# analog_out.net
KiCad netlist of a schematic drawn in EAGLE
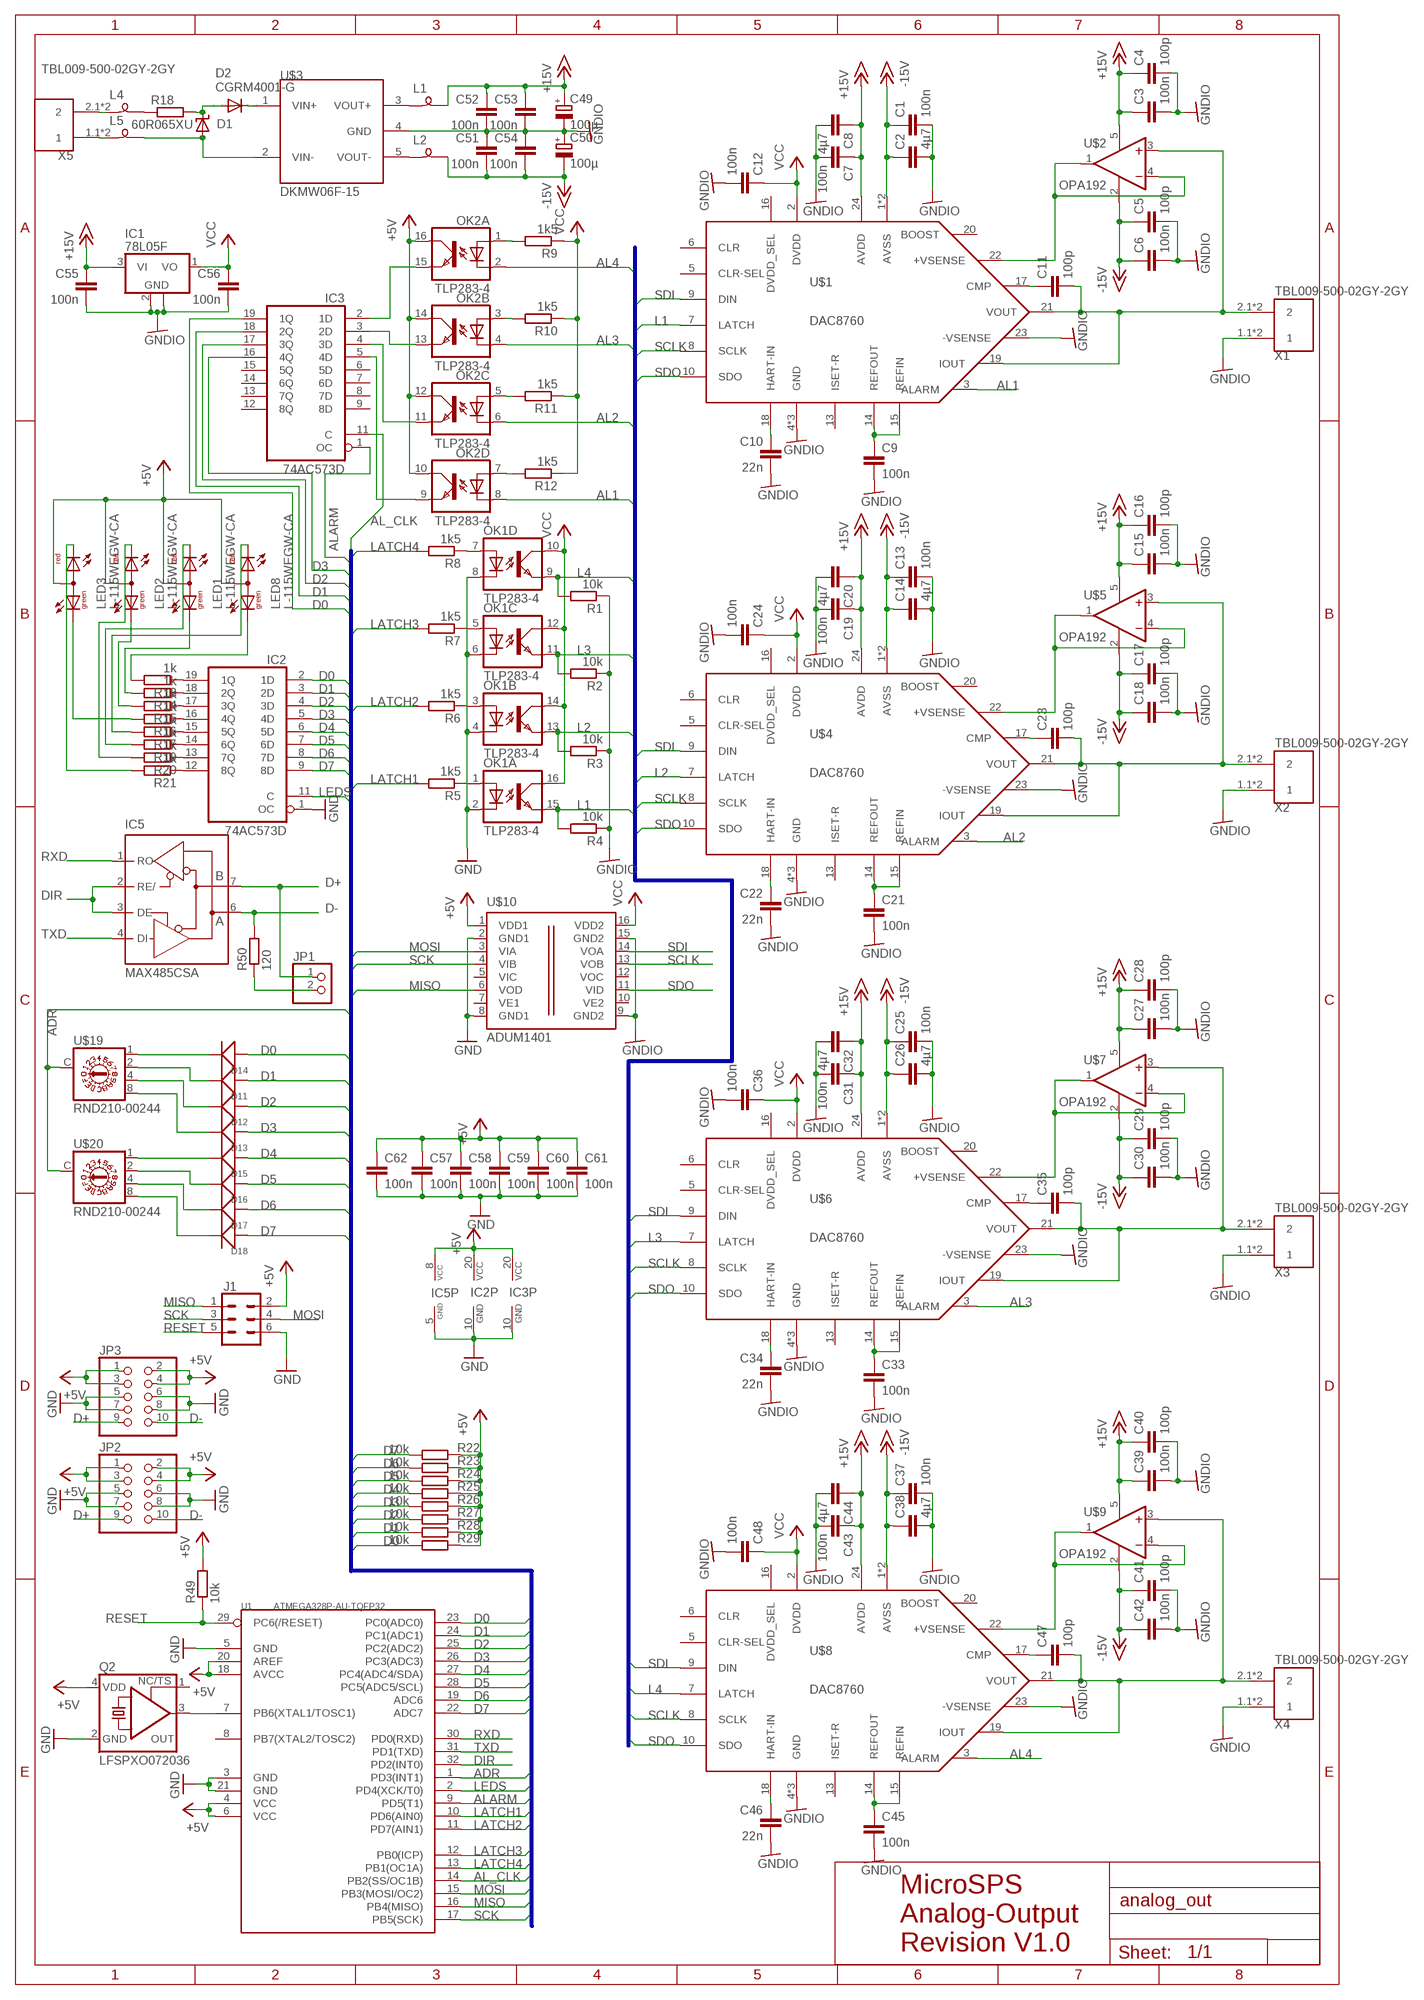
[diagram p0: schematic, sheet 1]

(export (version "E")
  (design (tool "Eeschema 10.0.6"))
  (components
    (comp (ref "C1")
      (value "100n")
      (footprint "eagle-import:C0805")
      (libsource (lib "eagle-import") (part "C-EUC0805"))
    )
    (comp (ref "C2")
      (value "4µ7")
      (footprint "eagle-import:C0805")
      (libsource (lib "eagle-import") (part "C-EUC0805"))
    )
    (comp (ref "C3")
      (value "100n")
      (footprint "eagle-import:C0805")
      (libsource (lib "eagle-import") (part "C-EUC0805"))
    )
    (comp (ref "C4")
      (value "100p")
      (footprint "eagle-import:C0805")
      (libsource (lib "eagle-import") (part "C-EUC0805"))
    )
    (comp (ref "C5")
      (value "100p")
      (footprint "eagle-import:C0805")
      (libsource (lib "eagle-import") (part "C-EUC0805"))
    )
    (comp (ref "C6")
      (value "100n")
      (footprint "eagle-import:C0805")
      (libsource (lib "eagle-import") (part "C-EUC0805"))
    )
    (comp (ref "C7")
      (value "100n")
      (footprint "eagle-import:C0805")
      (libsource (lib "eagle-import") (part "C-EUC0805"))
    )
    (comp (ref "C8")
      (value "4µ7")
      (footprint "eagle-import:C0805")
      (libsource (lib "eagle-import") (part "C-EUC0805"))
    )
    (comp (ref "C9")
      (value "100n")
      (footprint "eagle-import:C0805")
      (libsource (lib "eagle-import") (part "C-EUC0805"))
    )
    (comp (ref "C10")
      (value "22n")
      (footprint "eagle-import:C0805")
      (libsource (lib "eagle-import") (part "C-EUC0805"))
    )
    (comp (ref "C11")
      (value "100p")
      (footprint "eagle-import:C0805")
      (libsource (lib "eagle-import") (part "C-EUC0805"))
    )
    (comp (ref "C12")
      (value "100n")
      (footprint "eagle-import:C0805")
      (libsource (lib "eagle-import") (part "C-EUC0805"))
    )
    (comp (ref "C13")
      (value "100n")
      (footprint "eagle-import:C0805")
      (libsource (lib "eagle-import") (part "C-EUC0805"))
    )
    (comp (ref "C14")
      (value "4µ7")
      (footprint "eagle-import:C0805")
      (libsource (lib "eagle-import") (part "C-EUC0805"))
    )
    (comp (ref "C15")
      (value "100n")
      (footprint "eagle-import:C0805")
      (libsource (lib "eagle-import") (part "C-EUC0805"))
    )
    (comp (ref "C16")
      (value "100p")
      (footprint "eagle-import:C0805")
      (libsource (lib "eagle-import") (part "C-EUC0805"))
    )
    (comp (ref "C17")
      (value "100p")
      (footprint "eagle-import:C0805")
      (libsource (lib "eagle-import") (part "C-EUC0805"))
    )
    (comp (ref "C18")
      (value "100n")
      (footprint "eagle-import:C0805")
      (libsource (lib "eagle-import") (part "C-EUC0805"))
    )
    (comp (ref "C19")
      (value "100n")
      (footprint "eagle-import:C0805")
      (libsource (lib "eagle-import") (part "C-EUC0805"))
    )
    (comp (ref "C20")
      (value "4µ7")
      (footprint "eagle-import:C0805")
      (libsource (lib "eagle-import") (part "C-EUC0805"))
    )
    (comp (ref "C21")
      (value "100n")
      (footprint "eagle-import:C0805")
      (libsource (lib "eagle-import") (part "C-EUC0805"))
    )
    (comp (ref "C22")
      (value "22n")
      (footprint "eagle-import:C0805")
      (libsource (lib "eagle-import") (part "C-EUC0805"))
    )
    (comp (ref "C23")
      (value "100p")
      (footprint "eagle-import:C0805")
      (libsource (lib "eagle-import") (part "C-EUC0805"))
    )
    (comp (ref "C24")
      (value "100n")
      (footprint "eagle-import:C0805")
      (libsource (lib "eagle-import") (part "C-EUC0805"))
    )
    (comp (ref "C25")
      (value "100n")
      (footprint "eagle-import:C0805")
      (libsource (lib "eagle-import") (part "C-EUC0805"))
    )
    (comp (ref "C26")
      (value "4µ7")
      (footprint "eagle-import:C0805")
      (libsource (lib "eagle-import") (part "C-EUC0805"))
    )
    (comp (ref "C27")
      (value "100n")
      (footprint "eagle-import:C0805")
      (libsource (lib "eagle-import") (part "C-EUC0805"))
    )
    (comp (ref "C28")
      (value "100p")
      (footprint "eagle-import:C0805")
      (libsource (lib "eagle-import") (part "C-EUC0805"))
    )
    (comp (ref "C29")
      (value "100p")
      (footprint "eagle-import:C0805")
      (libsource (lib "eagle-import") (part "C-EUC0805"))
    )
    (comp (ref "C30")
      (value "100n")
      (footprint "eagle-import:C0805")
      (libsource (lib "eagle-import") (part "C-EUC0805"))
    )
    (comp (ref "C31")
      (value "100n")
      (footprint "eagle-import:C0805")
      (libsource (lib "eagle-import") (part "C-EUC0805"))
    )
    (comp (ref "C32")
      (value "4µ7")
      (footprint "eagle-import:C0805")
      (libsource (lib "eagle-import") (part "C-EUC0805"))
    )
    (comp (ref "C33")
      (value "100n")
      (footprint "eagle-import:C0805")
      (libsource (lib "eagle-import") (part "C-EUC0805"))
    )
    (comp (ref "C34")
      (value "22n")
      (footprint "eagle-import:C0805")
      (libsource (lib "eagle-import") (part "C-EUC0805"))
    )
    (comp (ref "C35")
      (value "100p")
      (footprint "eagle-import:C0805")
      (libsource (lib "eagle-import") (part "C-EUC0805"))
    )
    (comp (ref "C36")
      (value "100n")
      (footprint "eagle-import:C0805")
      (libsource (lib "eagle-import") (part "C-EUC0805"))
    )
    (comp (ref "C37")
      (value "100n")
      (footprint "eagle-import:C0805")
      (libsource (lib "eagle-import") (part "C-EUC0805"))
    )
    (comp (ref "C38")
      (value "4µ7")
      (footprint "eagle-import:C0805")
      (libsource (lib "eagle-import") (part "C-EUC0805"))
    )
    (comp (ref "C39")
      (value "100n")
      (footprint "eagle-import:C0805")
      (libsource (lib "eagle-import") (part "C-EUC0805"))
    )
    (comp (ref "C40")
      (value "100p")
      (footprint "eagle-import:C0805")
      (libsource (lib "eagle-import") (part "C-EUC0805"))
    )
    (comp (ref "C41")
      (value "100p")
      (footprint "eagle-import:C0805")
      (libsource (lib "eagle-import") (part "C-EUC0805"))
    )
    (comp (ref "C42")
      (value "100n")
      (footprint "eagle-import:C0805")
      (libsource (lib "eagle-import") (part "C-EUC0805"))
    )
    (comp (ref "C43")
      (value "100n")
      (footprint "eagle-import:C0805")
      (libsource (lib "eagle-import") (part "C-EUC0805"))
    )
    (comp (ref "C44")
      (value "4µ7")
      (footprint "eagle-import:C0805")
      (libsource (lib "eagle-import") (part "C-EUC0805"))
    )
    (comp (ref "C45")
      (value "100n")
      (footprint "eagle-import:C0805")
      (libsource (lib "eagle-import") (part "C-EUC0805"))
    )
    (comp (ref "C46")
      (value "22n")
      (footprint "eagle-import:C0805")
      (libsource (lib "eagle-import") (part "C-EUC0805"))
    )
    (comp (ref "C47")
      (value "100p")
      (footprint "eagle-import:C0805")
      (libsource (lib "eagle-import") (part "C-EUC0805"))
    )
    (comp (ref "C48")
      (value "100n")
      (footprint "eagle-import:C0805")
      (libsource (lib "eagle-import") (part "C-EUC0805"))
    )
    (comp (ref "C49")
      (value "100µ")
      (footprint "eagle-import:153CLV-0505")
      (libsource (lib "eagle-import") (part "CPOL-EU153CLV-0505"))
    )
    (comp (ref "C50")
      (value "100µ")
      (footprint "eagle-import:153CLV-0505")
      (libsource (lib "eagle-import") (part "CPOL-EU153CLV-0505"))
    )
    (comp (ref "C51")
      (value "100n")
      (footprint "eagle-import:C0805")
      (libsource (lib "eagle-import") (part "C-EUC0805"))
    )
    (comp (ref "C52")
      (value "100n")
      (footprint "eagle-import:C0805")
      (libsource (lib "eagle-import") (part "C-EUC0805"))
    )
    (comp (ref "C53")
      (value "100n")
      (footprint "eagle-import:C0805")
      (libsource (lib "eagle-import") (part "C-EUC0805"))
    )
    (comp (ref "C54")
      (value "100n")
      (footprint "eagle-import:C0805")
      (libsource (lib "eagle-import") (part "C-EUC0805"))
    )
    (comp (ref "C55")
      (value "100n")
      (footprint "eagle-import:C0805")
      (libsource (lib "eagle-import") (part "C-EUC0805"))
    )
    (comp (ref "C56")
      (value "100n")
      (footprint "eagle-import:C0805")
      (libsource (lib "eagle-import") (part "C-EUC0805"))
    )
    (comp (ref "C57")
      (value "100n")
      (footprint "eagle-import:C0805")
      (libsource (lib "eagle-import") (part "C-EUC0805"))
    )
    (comp (ref "C58")
      (value "100n")
      (footprint "eagle-import:C0805")
      (libsource (lib "eagle-import") (part "C-EUC0805"))
    )
    (comp (ref "C59")
      (value "100n")
      (footprint "eagle-import:C0805")
      (libsource (lib "eagle-import") (part "C-EUC0805"))
    )
    (comp (ref "C60")
      (value "100n")
      (footprint "eagle-import:C0805")
      (libsource (lib "eagle-import") (part "C-EUC0805"))
    )
    (comp (ref "C61")
      (value "100n")
      (footprint "eagle-import:C0805")
      (libsource (lib "eagle-import") (part "C-EUC0805"))
    )
    (comp (ref "C62")
      (value "100n")
      (footprint "eagle-import:C0805")
      (libsource (lib "eagle-import") (part "C-EUC0805"))
    )
    (comp (ref "D1")
      (value "SUPPRESSOR-SMBJ")
      (footprint "eagle-import:SMBJ")
      (libsource (lib "eagle-import") (part "SUPPRESSOR-SMBJ"))
    )
    (comp (ref "D2")
      (value "CGRM4001-G")
      (footprint "eagle-import:SOD-123_MINI-SMA")
      (libsource (lib "eagle-import") (part "CGRM400-G1"))
    )
    (comp (ref "D11")
      (value "DIODE'1N4148-SMD'")
      (footprint "eagle-import:LL-34")
      (libsource (lib "eagle-import") (part "DIODE'1N4148-SMD'"))
    )
    (comp (ref "D12")
      (value "DIODE'1N4148-SMD'")
      (footprint "eagle-import:LL-34")
      (libsource (lib "eagle-import") (part "DIODE'1N4148-SMD'"))
    )
    (comp (ref "D13")
      (value "DIODE'1N4148-SMD'")
      (footprint "eagle-import:LL-34")
      (libsource (lib "eagle-import") (part "DIODE'1N4148-SMD'"))
    )
    (comp (ref "D14")
      (value "DIODE'1N4148-SMD'")
      (footprint "eagle-import:LL-34")
      (libsource (lib "eagle-import") (part "DIODE'1N4148-SMD'"))
    )
    (comp (ref "D15")
      (value "DIODE'1N4148-SMD'")
      (footprint "eagle-import:LL-34")
      (libsource (lib "eagle-import") (part "DIODE'1N4148-SMD'"))
    )
    (comp (ref "D16")
      (value "DIODE'1N4148-SMD'")
      (footprint "eagle-import:LL-34")
      (libsource (lib "eagle-import") (part "DIODE'1N4148-SMD'"))
    )
    (comp (ref "D17")
      (value "DIODE'1N4148-SMD'")
      (footprint "eagle-import:LL-34")
      (libsource (lib "eagle-import") (part "DIODE'1N4148-SMD'"))
    )
    (comp (ref "D18")
      (value "DIODE'1N4148-SMD'")
      (footprint "eagle-import:LL-34")
      (libsource (lib "eagle-import") (part "DIODE'1N4148-SMD'"))
    )
    (comp (ref "IC1")
      (value "78L05F")
      (footprint "eagle-import:SOT89")
      (libsource (lib "eagle-import") (part "78LF05"))
    )
    (comp (ref "IC2")
      (value "74AC573D")
      (footprint "eagle-import:SO20W")
      (libsource (lib "eagle-import") (part "74573DAC"))
    )
    (comp (ref "IC3")
      (value "74AC573D")
      (footprint "eagle-import:SO20W")
      (libsource (lib "eagle-import") (part "74573DAC"))
    )
    (comp (ref "IC5")
      (value "MAX485CSA")
      (footprint "eagle-import:SO08")
      (fields (field (name "MF") "MAXIM") (field (name "MPN") "MAX481CSA"))
      (libsource (lib "eagle-import") (part "MAX481CSA"))
    )
    (comp (ref "J1")
      (value "CONN_03X2FEMALE_SMD")
      (footprint "eagle-import:2X3_SMD")
      (libsource (lib "eagle-import") (part "CONN_03X2FEMALE_SMD"))
    )
    (comp (ref "JP1")
      (value "PINHD-1X2")
      (footprint "eagle-import:1X02")
      (libsource (lib "eagle-import") (part "PINHD-1X2"))
    )
    (comp (ref "JP2")
      (value "PINHD-2X5/90")
      (footprint "eagle-import:2X05_90")
      (libsource (lib "eagle-import") (part "PINHD-2X5/90"))
    )
    (comp (ref "JP3")
      (value "PINHD-2X5/90")
      (footprint "eagle-import:2X05_90")
      (libsource (lib "eagle-import") (part "PINHD-2X5/90"))
    )
    (comp (ref "L1")
      (value "SM-B5")
      (footprint "eagle-import:SM-B5")
      (libsource (lib "eagle-import") (part "SM-B5"))
    )
    (comp (ref "L2")
      (value "SM-B5")
      (footprint "eagle-import:SM-B5")
      (libsource (lib "eagle-import") (part "SM-B5"))
    )
    (comp (ref "L4")
      (value "SM-B5")
      (footprint "eagle-import:SM-B5")
      (libsource (lib "eagle-import") (part "SM-B5"))
    )
    (comp (ref "L5")
      (value "SM-B5")
      (footprint "eagle-import:SM-B5")
      (libsource (lib "eagle-import") (part "SM-B5"))
    )
    (comp (ref "LED1")
      (value "L-115WEGW-CA")
      (footprint "eagle-import:DUOLED-A-3MM")
      (libsource (lib "eagle-import") (part "L-115WEGW-CA"))
    )
    (comp (ref "LED2")
      (value "L-115WEGW-CA")
      (footprint "eagle-import:DUOLED-A-3MM")
      (libsource (lib "eagle-import") (part "L-115WEGW-CA"))
    )
    (comp (ref "LED3")
      (value "L-115WEGW-CA")
      (footprint "eagle-import:DUOLED-A-3MM")
      (libsource (lib "eagle-import") (part "L-115WEGW-CA"))
    )
    (comp (ref "LED8")
      (value "L-115WEGW-CA")
      (footprint "eagle-import:DUOLED-A-3MM")
      (libsource (lib "eagle-import") (part "L-115WEGW-CA"))
    )
    (comp (ref "OK1")
      (value "TLP283-4")
      (footprint "eagle-import:MINI-FLAT-16")
      (libsource (lib "eagle-import") (part "TLP283-4"))
    )
    (comp (ref "OK2")
      (value "TLP283-4")
      (footprint "eagle-import:MINI-FLAT-16")
      (libsource (lib "eagle-import") (part "TLP283-4"))
    )
    (comp (ref "Q2")
      (value "LFSPXO072036")
      (footprint "eagle-import:5.0X3.2_KXO-56")
      (libsource (lib "eagle-import") (part "KXO-PXO/XO-56-56"))
    )
    (comp (ref "R1")
      (value "10k")
      (footprint "eagle-import:R0805")
      (libsource (lib "eagle-import") (part "R-EU_R0805"))
    )
    (comp (ref "R2")
      (value "10k")
      (footprint "eagle-import:R0805")
      (libsource (lib "eagle-import") (part "R-EU_R0805"))
    )
    (comp (ref "R3")
      (value "10k")
      (footprint "eagle-import:R0805")
      (libsource (lib "eagle-import") (part "R-EU_R0805"))
    )
    (comp (ref "R4")
      (value "10k")
      (footprint "eagle-import:R0805")
      (libsource (lib "eagle-import") (part "R-EU_R0805"))
    )
    (comp (ref "R5")
      (value "1k5")
      (footprint "eagle-import:R0805")
      (libsource (lib "eagle-import") (part "R-EU_R0805"))
    )
    (comp (ref "R6")
      (value "1k5")
      (footprint "eagle-import:R0805")
      (libsource (lib "eagle-import") (part "R-EU_R0805"))
    )
    (comp (ref "R7")
      (value "1k5")
      (footprint "eagle-import:R0805")
      (libsource (lib "eagle-import") (part "R-EU_R0805"))
    )
    (comp (ref "R8")
      (value "1k5")
      (footprint "eagle-import:R0805")
      (libsource (lib "eagle-import") (part "R-EU_R0805"))
    )
    (comp (ref "R9")
      (value "1k5")
      (footprint "eagle-import:R0805")
      (libsource (lib "eagle-import") (part "R-EU_R0805"))
    )
    (comp (ref "R10")
      (value "1k5")
      (footprint "eagle-import:R0805")
      (libsource (lib "eagle-import") (part "R-EU_R0805"))
    )
    (comp (ref "R11")
      (value "1k5")
      (footprint "eagle-import:R0805")
      (libsource (lib "eagle-import") (part "R-EU_R0805"))
    )
    (comp (ref "R12")
      (value "1k5")
      (footprint "eagle-import:R0805")
      (libsource (lib "eagle-import") (part "R-EU_R0805"))
    )
    (comp (ref "R13")
      (value "1k")
      (footprint "eagle-import:R0805")
      (libsource (lib "eagle-import") (part "R-EU_R0805"))
    )
    (comp (ref "R14")
      (value "1k")
      (footprint "eagle-import:R0805")
      (libsource (lib "eagle-import") (part "R-EU_R0805"))
    )
    (comp (ref "R15")
      (value "1k")
      (footprint "eagle-import:R0805")
      (libsource (lib "eagle-import") (part "R-EU_R0805"))
    )
    (comp (ref "R16")
      (value "1k")
      (footprint "eagle-import:R0805")
      (libsource (lib "eagle-import") (part "R-EU_R0805"))
    )
    (comp (ref "R17")
      (value "1k")
      (footprint "eagle-import:R0805")
      (libsource (lib "eagle-import") (part "R-EU_R0805"))
    )
    (comp (ref "R18")
      (value "60R065XU")
      (footprint "eagle-import:0204_5")
      (libsource (lib "eagle-import") (part "R-EU_0204/5"))
    )
    (comp (ref "R19")
      (value "1k")
      (footprint "eagle-import:R0805")
      (libsource (lib "eagle-import") (part "R-EU_R0805"))
    )
    (comp (ref "R20")
      (value "1k")
      (footprint "eagle-import:R0805")
      (libsource (lib "eagle-import") (part "R-EU_R0805"))
    )
    (comp (ref "R21")
      (value "1k")
      (footprint "eagle-import:R0805")
      (libsource (lib "eagle-import") (part "R-EU_R0805"))
    )
    (comp (ref "R22")
      (value "10k")
      (footprint "eagle-import:R0805")
      (libsource (lib "eagle-import") (part "R-EU_R0805"))
    )
    (comp (ref "R23")
      (value "10k")
      (footprint "eagle-import:R0805")
      (libsource (lib "eagle-import") (part "R-EU_R0805"))
    )
    (comp (ref "R24")
      (value "10k")
      (footprint "eagle-import:R0805")
      (libsource (lib "eagle-import") (part "R-EU_R0805"))
    )
    (comp (ref "R25")
      (value "10k")
      (footprint "eagle-import:R0805")
      (libsource (lib "eagle-import") (part "R-EU_R0805"))
    )
    (comp (ref "R26")
      (value "10k")
      (footprint "eagle-import:R0805")
      (libsource (lib "eagle-import") (part "R-EU_R0805"))
    )
    (comp (ref "R27")
      (value "10k")
      (footprint "eagle-import:R0805")
      (libsource (lib "eagle-import") (part "R-EU_R0805"))
    )
    (comp (ref "R28")
      (value "10k")
      (footprint "eagle-import:R0805")
      (libsource (lib "eagle-import") (part "R-EU_R0805"))
    )
    (comp (ref "R29")
      (value "10k")
      (footprint "eagle-import:R0805")
      (libsource (lib "eagle-import") (part "R-EU_R0805"))
    )
    (comp (ref "R49")
      (value "10k")
      (footprint "eagle-import:R0805")
      (libsource (lib "eagle-import") (part "R-EU_R0805"))
    )
    (comp (ref "R50")
      (value "120")
      (footprint "eagle-import:R0805")
      (libsource (lib "eagle-import") (part "R-EU_R0805"))
    )
    (comp (ref "U$1")
      (value "DAC8760")
      (footprint "eagle-import:HTSSOP24PWP")
      (libsource (lib "eagle-import") (part "DAC8760"))
    )
    (comp (ref "U$2")
      (value "OPA192")
      (footprint "eagle-import:SOT23-DBV")
      (libsource (lib "eagle-import") (part "OPA192"))
    )
    (comp (ref "U$3")
      (value "DKMW06F-15")
      (footprint "eagle-import:DKWM06")
      (libsource (lib "eagle-import") (part "DKMW06F-15"))
    )
    (comp (ref "U$4")
      (value "DAC8760")
      (footprint "eagle-import:HTSSOP24PWP")
      (libsource (lib "eagle-import") (part "DAC8760"))
    )
    (comp (ref "U$5")
      (value "OPA192")
      (footprint "eagle-import:SOT23-DBV")
      (libsource (lib "eagle-import") (part "OPA192"))
    )
    (comp (ref "U$6")
      (value "DAC8760")
      (footprint "eagle-import:HTSSOP24PWP")
      (libsource (lib "eagle-import") (part "DAC8760"))
    )
    (comp (ref "U$7")
      (value "OPA192")
      (footprint "eagle-import:SOT23-DBV")
      (libsource (lib "eagle-import") (part "OPA192"))
    )
    (comp (ref "U$8")
      (value "DAC8760")
      (footprint "eagle-import:HTSSOP24PWP")
      (libsource (lib "eagle-import") (part "DAC8760"))
    )
    (comp (ref "U$9")
      (value "OPA192")
      (footprint "eagle-import:SOT23-DBV")
      (libsource (lib "eagle-import") (part "OPA192"))
    )
    (comp (ref "U$10")
      (value "ADUM1401")
      (footprint "eagle-import:SO-16W")
      (libsource (lib "eagle-import") (part "ADUM1401"))
    )
    (comp (ref "U$19")
      (value "RND210-00244")
      (footprint "eagle-import:RND210-00244")
      (libsource (lib "eagle-import") (part "RND210-00244"))
    )
    (comp (ref "U$20")
      (value "RND210-00244")
      (footprint "eagle-import:RND210-00244")
      (libsource (lib "eagle-import") (part "RND210-00244"))
    )
    (comp (ref "U1")
      (value "ATMEGA328P-AU-TQFP32")
      (footprint "eagle-import:TQFP32-0.8-7X7MM")
      (fields (field (name "MPN") "ATMEGA328P-AU"))
      (libsource (lib "eagle-import") (part "MCU-ATMEGA328P-AU(TQFP32)"))
    )
    (comp (ref "X1")
      (value "TBL009-500-02GY-2GY")
      (footprint "eagle-import:TBL009-500-02GY-2GY")
      (libsource (lib "eagle-import") (part "TBL009-500-02GY-2GY"))
    )
    (comp (ref "X2")
      (value "TBL009-500-02GY-2GY")
      (footprint "eagle-import:TBL009-500-02GY-2GY")
      (libsource (lib "eagle-import") (part "TBL009-500-02GY-2GY"))
    )
    (comp (ref "X3")
      (value "TBL009-500-02GY-2GY")
      (footprint "eagle-import:TBL009-500-02GY-2GY")
      (libsource (lib "eagle-import") (part "TBL009-500-02GY-2GY"))
    )
    (comp (ref "X4")
      (value "TBL009-500-02GY-2GY")
      (footprint "eagle-import:TBL009-500-02GY-2GY")
      (libsource (lib "eagle-import") (part "TBL009-500-02GY-2GY"))
    )
    (comp (ref "X5")
      (value "TBL009-500-02GY-2GY")
      (footprint "eagle-import:TBL009-500-02GY-2GY")
      (libsource (lib "eagle-import") (part "TBL009-500-02GY-2GY"))
    )
  )
  (nets
    (net (code "1") (name "+5V") (class "Default")
      (node (ref "C57") (pin "1") (pinfunction "1_1") (pintype "passive"))
      (node (ref "C58") (pin "1") (pinfunction "1_1") (pintype "passive"))
      (node (ref "C59") (pin "1") (pinfunction "1_1") (pintype "passive"))
      (node (ref "C60") (pin "1") (pinfunction "1_1") (pintype "passive"))
      (node (ref "C61") (pin "1") (pinfunction "1_1") (pintype "passive"))
      (node (ref "C62") (pin "1") (pinfunction "1_1") (pintype "passive"))
      (node (ref "IC2") (pin "20") (pinfunction "VCC_20") (pintype "power_in"))
      (node (ref "IC3") (pin "20") (pinfunction "VCC_20") (pintype "power_in"))
      (node (ref "IC5") (pin "8") (pinfunction "VCC_8") (pintype "power_in"))
      (node (ref "J1") (pin "2") (pinfunction "2_2") (pintype "bidirectional"))
      (node (ref "JP2") (pin "1") (pinfunction "1_1") (pintype "passive"))
      (node (ref "JP2") (pin "2") (pinfunction "2_2") (pintype "passive"))
      (node (ref "JP2") (pin "3") (pinfunction "3_3") (pintype "passive"))
      (node (ref "JP2") (pin "4") (pinfunction "4_4") (pintype "passive"))
      (node (ref "JP3") (pin "1") (pinfunction "1_1") (pintype "passive"))
      (node (ref "JP3") (pin "2") (pinfunction "2_2") (pintype "passive"))
      (node (ref "JP3") (pin "3") (pinfunction "3_3") (pintype "passive"))
      (node (ref "JP3") (pin "4") (pinfunction "4_4") (pintype "passive"))
      (node (ref "LED1") (pin "2") (pinfunction "A_2") (pintype "passive"))
      (node (ref "LED2") (pin "2") (pinfunction "A_2") (pintype "passive"))
      (node (ref "LED3") (pin "2") (pinfunction "A_2") (pintype "passive"))
      (node (ref "LED8") (pin "2") (pinfunction "A_2") (pintype "passive"))
      (node (ref "OK2") (pin "10") (pinfunction "COL_10") (pintype "passive"))
      (node (ref "OK2") (pin "12") (pinfunction "COL_12") (pintype "passive"))
      (node (ref "OK2") (pin "14") (pinfunction "COL_14") (pintype "passive"))
      (node (ref "OK2") (pin "16") (pinfunction "COL_16") (pintype "passive"))
      (node (ref "Q2") (pin "4") (pinfunction "VDD_4") (pintype "power_in"))
      (node (ref "R22") (pin "1") (pinfunction "1_1") (pintype "passive"))
      (node (ref "R23") (pin "1") (pinfunction "1_1") (pintype "passive"))
      (node (ref "R24") (pin "1") (pinfunction "1_1") (pintype "passive"))
      (node (ref "R25") (pin "1") (pinfunction "1_1") (pintype "passive"))
      (node (ref "R26") (pin "1") (pinfunction "1_1") (pintype "passive"))
      (node (ref "R27") (pin "1") (pinfunction "1_1") (pintype "passive"))
      (node (ref "R28") (pin "1") (pinfunction "1_1") (pintype "passive"))
      (node (ref "R29") (pin "1") (pinfunction "1_1") (pintype "passive"))
      (node (ref "R49") (pin "2") (pinfunction "2_2") (pintype "passive"))
      (node (ref "U$10") (pin "1") (pinfunction "VDD1_1") (pintype "input"))
      (node (ref "U1") (pin "18") (pinfunction "AVCC_18") (pintype "bidirectional"))
      (node (ref "U1") (pin "20") (pinfunction "AREF_20") (pintype "bidirectional"))
      (node (ref "U1") (pin "4") (pinfunction "VCC_4") (pintype "bidirectional"))
      (node (ref "U1") (pin "6") (pinfunction "VCC_6") (pintype "bidirectional"))
    )
    (net (code "2") (name "+15V") (class "Default")
      (node (ref "C15") (pin "1") (pinfunction "1_1") (pintype "passive"))
      (node (ref "C16") (pin "1") (pinfunction "1_1") (pintype "passive"))
      (node (ref "C19") (pin "1") (pinfunction "1_1") (pintype "passive"))
      (node (ref "C20") (pin "1") (pinfunction "1_1") (pintype "passive"))
      (node (ref "C27") (pin "1") (pinfunction "1_1") (pintype "passive"))
      (node (ref "C28") (pin "1") (pinfunction "1_1") (pintype "passive"))
      (node (ref "C3") (pin "1") (pinfunction "1_1") (pintype "passive"))
      (node (ref "C31") (pin "1") (pinfunction "1_1") (pintype "passive"))
      (node (ref "C32") (pin "1") (pinfunction "1_1") (pintype "passive"))
      (node (ref "C39") (pin "1") (pinfunction "1_1") (pintype "passive"))
      (node (ref "C4") (pin "1") (pinfunction "1_1") (pintype "passive"))
      (node (ref "C40") (pin "1") (pinfunction "1_1") (pintype "passive"))
      (node (ref "C43") (pin "1") (pinfunction "1_1") (pintype "passive"))
      (node (ref "C44") (pin "1") (pinfunction "1_1") (pintype "passive"))
      (node (ref "C49") (pin "+") (pinfunction "+_+") (pintype "passive"))
      (node (ref "C52") (pin "1") (pinfunction "1_1") (pintype "passive"))
      (node (ref "C53") (pin "1") (pinfunction "1_1") (pintype "passive"))
      (node (ref "C55") (pin "1") (pinfunction "1_1") (pintype "passive"))
      (node (ref "C7") (pin "1") (pinfunction "1_1") (pintype "passive"))
      (node (ref "C8") (pin "1") (pinfunction "1_1") (pintype "passive"))
      (node (ref "IC1") (pin "3") (pinfunction "VI_3") (pintype "input"))
      (node (ref "L1") (pin "1") (pinfunction "1_1") (pintype "passive"))
      (node (ref "U$1") (pin "24") (pinfunction "AVDD_24") (pintype "bidirectional"))
      (node (ref "U$2") (pin "5") (pinfunction "V+_5") (pintype "power_in"))
      (node (ref "U$4") (pin "24") (pinfunction "AVDD_24") (pintype "bidirectional"))
      (node (ref "U$5") (pin "5") (pinfunction "V+_5") (pintype "power_in"))
      (node (ref "U$6") (pin "24") (pinfunction "AVDD_24") (pintype "bidirectional"))
      (node (ref "U$7") (pin "5") (pinfunction "V+_5") (pintype "power_in"))
      (node (ref "U$8") (pin "24") (pinfunction "AVDD_24") (pintype "bidirectional"))
      (node (ref "U$9") (pin "5") (pinfunction "V+_5") (pintype "power_in"))
    )
    (net (code "3") (name "-15V") (class "Default")
      (node (ref "C1") (pin "1") (pinfunction "1_1") (pintype "passive"))
      (node (ref "C13") (pin "1") (pinfunction "1_1") (pintype "passive"))
      (node (ref "C14") (pin "1") (pinfunction "1_1") (pintype "passive"))
      (node (ref "C17") (pin "1") (pinfunction "1_1") (pintype "passive"))
      (node (ref "C18") (pin "1") (pinfunction "1_1") (pintype "passive"))
      (node (ref "C2") (pin "1") (pinfunction "1_1") (pintype "passive"))
      (node (ref "C25") (pin "1") (pinfunction "1_1") (pintype "passive"))
      (node (ref "C26") (pin "1") (pinfunction "1_1") (pintype "passive"))
      (node (ref "C29") (pin "1") (pinfunction "1_1") (pintype "passive"))
      (node (ref "C30") (pin "1") (pinfunction "1_1") (pintype "passive"))
      (node (ref "C37") (pin "1") (pinfunction "1_1") (pintype "passive"))
      (node (ref "C38") (pin "1") (pinfunction "1_1") (pintype "passive"))
      (node (ref "C41") (pin "1") (pinfunction "1_1") (pintype "passive"))
      (node (ref "C42") (pin "1") (pinfunction "1_1") (pintype "passive"))
      (node (ref "C5") (pin "1") (pinfunction "1_1") (pintype "passive"))
      (node (ref "C50") (pin "-") (pinfunction "-_-") (pintype "passive"))
      (node (ref "C51") (pin "2") (pinfunction "2_2") (pintype "passive"))
      (node (ref "C54") (pin "2") (pinfunction "2_2") (pintype "passive"))
      (node (ref "C6") (pin "1") (pinfunction "1_1") (pintype "passive"))
      (node (ref "L2") (pin "1") (pinfunction "1_1") (pintype "passive"))
      (node (ref "U$1") (pin "1") (pinfunction "AVSS_1") (pintype "bidirectional"))
      (node (ref "U$1") (pin "EXP") (pinfunction "AVSS_EXP") (pintype "bidirectional"))
      (node (ref "U$2") (pin "2") (pinfunction "V-_2") (pintype "power_in"))
      (node (ref "U$4") (pin "1") (pinfunction "AVSS_1") (pintype "bidirectional"))
      (node (ref "U$4") (pin "EXP") (pinfunction "AVSS_EXP") (pintype "bidirectional"))
      (node (ref "U$5") (pin "2") (pinfunction "V-_2") (pintype "power_in"))
      (node (ref "U$6") (pin "1") (pinfunction "AVSS_1") (pintype "bidirectional"))
      (node (ref "U$6") (pin "EXP") (pinfunction "AVSS_EXP") (pintype "bidirectional"))
      (node (ref "U$7") (pin "2") (pinfunction "V-_2") (pintype "power_in"))
      (node (ref "U$8") (pin "1") (pinfunction "AVSS_1") (pintype "bidirectional"))
      (node (ref "U$8") (pin "EXP") (pinfunction "AVSS_EXP") (pintype "bidirectional"))
      (node (ref "U$9") (pin "2") (pinfunction "V-_2") (pintype "power_in"))
    )
    (net (code "4") (name "/ADR") (class "Default")
      (node (ref "U$19") (pin "C") (pinfunction "C_C") (pintype "passive"))
      (node (ref "U$20") (pin "C") (pinfunction "C_C") (pintype "passive"))
      (node (ref "U1") (pin "1") (pinfunction "PD3(INT1)_1") (pintype "bidirectional"))
    )
    (net (code "5") (name "/AL1") (class "Default")
      (node (ref "OK2") (pin "8") (pinfunction "C_8") (pintype "passive"))
      (node (ref "U$1") (pin "3") (pinfunction "ALARM_3") (pintype "bidirectional"))
    )
    (net (code "6") (name "/AL2") (class "Default")
      (node (ref "OK2") (pin "6") (pinfunction "C_6") (pintype "passive"))
      (node (ref "U$4") (pin "3") (pinfunction "ALARM_3") (pintype "bidirectional"))
    )
    (net (code "7") (name "/AL3") (class "Default")
      (node (ref "OK2") (pin "4") (pinfunction "C_4") (pintype "passive"))
      (node (ref "U$6") (pin "3") (pinfunction "ALARM_3") (pintype "bidirectional"))
    )
    (net (code "8") (name "/AL4") (class "Default")
      (node (ref "OK2") (pin "2") (pinfunction "C_2") (pintype "passive"))
      (node (ref "U$8") (pin "3") (pinfunction "ALARM_3") (pintype "bidirectional"))
    )
    (net (code "9") (name "/ALARM") (class "Default")
      (node (ref "IC3") (pin "1") (pinfunction "OC_1") (pintype "input"))
      (node (ref "U1") (pin "9") (pinfunction "PD5(T1)_9") (pintype "bidirectional"))
    )
    (net (code "10") (name "/AL_CLK") (class "Default")
      (node (ref "IC3") (pin "11") (pinfunction "C_11") (pintype "input"))
      (node (ref "U1") (pin "14") (pinfunction "PB2(SS/OC1B)_14") (pintype "bidirectional"))
    )
    (net (code "11") (name "/D+") (class "Default")
      (node (ref "IC5") (pin "7") (pinfunction "B_7") (pintype "passive"))
      (node (ref "JP1") (pin "1") (pinfunction "1_1") (pintype "passive"))
      (node (ref "JP2") (pin "9") (pinfunction "9_9") (pintype "passive"))
      (node (ref "JP3") (pin "9") (pinfunction "9_9") (pintype "passive"))
    )
    (net (code "12") (name "/D-") (class "Default")
      (node (ref "IC5") (pin "6") (pinfunction "A_6") (pintype "passive"))
      (node (ref "JP2") (pin "10") (pinfunction "10_10") (pintype "passive"))
      (node (ref "JP3") (pin "10") (pinfunction "10_10") (pintype "passive"))
      (node (ref "R50") (pin "2") (pinfunction "2_2") (pintype "passive"))
    )
    (net (code "13") (name "/D0") (class "Default")
      (node (ref "D14") (pin "A") (pinfunction "+_A") (pintype "passive"))
      (node (ref "IC2") (pin "2") (pinfunction "1D_2") (pintype "input"))
      (node (ref "IC3") (pin "19") (pinfunction "1Q_19") (pintype "tri_state"))
      (node (ref "R29") (pin "2") (pinfunction "2_2") (pintype "passive"))
      (node (ref "U1") (pin "23") (pinfunction "PC0(ADC0)_23") (pintype "bidirectional"))
    )
    (net (code "14") (name "/D1") (class "Default")
      (node (ref "D11") (pin "A") (pinfunction "+_A") (pintype "passive"))
      (node (ref "IC2") (pin "3") (pinfunction "2D_3") (pintype "input"))
      (node (ref "IC3") (pin "18") (pinfunction "2Q_18") (pintype "tri_state"))
      (node (ref "R28") (pin "2") (pinfunction "2_2") (pintype "passive"))
      (node (ref "U1") (pin "24") (pinfunction "PC1(ADC1)_24") (pintype "bidirectional"))
    )
    (net (code "15") (name "/D2") (class "Default")
      (node (ref "D12") (pin "A") (pinfunction "+_A") (pintype "passive"))
      (node (ref "IC2") (pin "4") (pinfunction "3D_4") (pintype "input"))
      (node (ref "IC3") (pin "17") (pinfunction "3Q_17") (pintype "tri_state"))
      (node (ref "R27") (pin "2") (pinfunction "2_2") (pintype "passive"))
      (node (ref "U1") (pin "25") (pinfunction "PC2(ADC2)_25") (pintype "bidirectional"))
    )
    (net (code "16") (name "/D3") (class "Default")
      (node (ref "D13") (pin "A") (pinfunction "+_A") (pintype "passive"))
      (node (ref "IC2") (pin "5") (pinfunction "4D_5") (pintype "input"))
      (node (ref "IC3") (pin "16") (pinfunction "4Q_16") (pintype "tri_state"))
      (node (ref "R26") (pin "2") (pinfunction "2_2") (pintype "passive"))
      (node (ref "U1") (pin "26") (pinfunction "PC3(ADC3)_26") (pintype "bidirectional"))
    )
    (net (code "17") (name "/D4") (class "Default")
      (node (ref "D15") (pin "A") (pinfunction "+_A") (pintype "passive"))
      (node (ref "IC2") (pin "6") (pinfunction "5D_6") (pintype "input"))
      (node (ref "R25") (pin "2") (pinfunction "2_2") (pintype "passive"))
      (node (ref "U1") (pin "27") (pinfunction "PC4(ADC4/SDA)_27") (pintype "bidirectional"))
    )
    (net (code "18") (name "/D5") (class "Default")
      (node (ref "D16") (pin "A") (pinfunction "+_A") (pintype "passive"))
      (node (ref "IC2") (pin "7") (pinfunction "6D_7") (pintype "input"))
      (node (ref "R24") (pin "2") (pinfunction "2_2") (pintype "passive"))
      (node (ref "U1") (pin "28") (pinfunction "PC5(ADC5/SCL)_28") (pintype "bidirectional"))
    )
    (net (code "19") (name "/D6") (class "Default")
      (node (ref "D17") (pin "A") (pinfunction "+_A") (pintype "passive"))
      (node (ref "IC2") (pin "8") (pinfunction "7D_8") (pintype "input"))
      (node (ref "R23") (pin "2") (pinfunction "2_2") (pintype "passive"))
      (node (ref "U1") (pin "19") (pinfunction "ADC6_19") (pintype "bidirectional"))
    )
    (net (code "20") (name "/D7") (class "Default")
      (node (ref "D18") (pin "A") (pinfunction "+_A") (pintype "passive"))
      (node (ref "IC2") (pin "9") (pinfunction "8D_9") (pintype "input"))
      (node (ref "R22") (pin "2") (pinfunction "2_2") (pintype "passive"))
      (node (ref "U1") (pin "22") (pinfunction "ADC7_22") (pintype "bidirectional"))
    )
    (net (code "21") (name "/DIR") (class "Default")
      (node (ref "IC5") (pin "2") (pinfunction "RE/_2") (pintype "input"))
      (node (ref "IC5") (pin "3") (pinfunction "DE_3") (pintype "input"))
      (node (ref "U1") (pin "32") (pinfunction "PD2(INT0)_32") (pintype "bidirectional"))
    )
    (net (code "22") (name "/L1") (class "Default")
      (node (ref "OK1") (pin "15") (pinfunction "EMIT_15") (pintype "passive"))
      (node (ref "R4") (pin "2") (pinfunction "2_2") (pintype "passive"))
      (node (ref "U$1") (pin "7") (pinfunction "LATCH_7") (pintype "bidirectional"))
    )
    (net (code "23") (name "/L2") (class "Default")
      (node (ref "OK1") (pin "13") (pinfunction "EMIT_13") (pintype "passive"))
      (node (ref "R3") (pin "2") (pinfunction "2_2") (pintype "passive"))
      (node (ref "U$4") (pin "7") (pinfunction "LATCH_7") (pintype "bidirectional"))
    )
    (net (code "24") (name "/L3") (class "Default")
      (node (ref "OK1") (pin "11") (pinfunction "EMIT_11") (pintype "passive"))
      (node (ref "R2") (pin "2") (pinfunction "2_2") (pintype "passive"))
      (node (ref "U$6") (pin "7") (pinfunction "LATCH_7") (pintype "bidirectional"))
    )
    (net (code "25") (name "/L4") (class "Default")
      (node (ref "OK1") (pin "9") (pinfunction "EMIT_9") (pintype "passive"))
      (node (ref "R1") (pin "2") (pinfunction "2_2") (pintype "passive"))
      (node (ref "U$8") (pin "7") (pinfunction "LATCH_7") (pintype "bidirectional"))
    )
    (net (code "26") (name "/LATCH1") (class "Default")
      (node (ref "R5") (pin "2") (pinfunction "2_2") (pintype "passive"))
      (node (ref "U1") (pin "10") (pinfunction "PD6(AIN0)_10") (pintype "bidirectional"))
    )
    (net (code "27") (name "/LATCH2") (class "Default")
      (node (ref "R6") (pin "2") (pinfunction "2_2") (pintype "passive"))
      (node (ref "U1") (pin "11") (pinfunction "PD7(AIN1)_11") (pintype "bidirectional"))
    )
    (net (code "28") (name "/LATCH3") (class "Default")
      (node (ref "R7") (pin "2") (pinfunction "2_2") (pintype "passive"))
      (node (ref "U1") (pin "12") (pinfunction "PB0(ICP)_12") (pintype "bidirectional"))
    )
    (net (code "29") (name "/LATCH4") (class "Default")
      (node (ref "R8") (pin "2") (pinfunction "2_2") (pintype "passive"))
      (node (ref "U1") (pin "13") (pinfunction "PB1(OC1A)_13") (pintype "bidirectional"))
    )
    (net (code "30") (name "/LEDS") (class "Default")
      (node (ref "IC2") (pin "11") (pinfunction "C_11") (pintype "input"))
      (node (ref "U1") (pin "2") (pinfunction "PD4(XCK/T0)_2") (pintype "bidirectional"))
    )
    (net (code "31") (name "/MISO") (class "Default")
      (node (ref "J1") (pin "1") (pinfunction "1_1") (pintype "bidirectional"))
      (node (ref "U$10") (pin "6") (pinfunction "VOD_6") (pintype "input"))
      (node (ref "U1") (pin "16") (pinfunction "PB4(MISO)_16") (pintype "bidirectional"))
    )
    (net (code "32") (name "/MOSI") (class "Default")
      (node (ref "J1") (pin "4") (pinfunction "4_4") (pintype "bidirectional"))
      (node (ref "U$10") (pin "3") (pinfunction "VIA_3") (pintype "input"))
      (node (ref "U1") (pin "15") (pinfunction "PB3(MOSI/OC2)_15") (pintype "bidirectional"))
    )
    (net (code "33") (name "/RESET") (class "Default")
      (node (ref "J1") (pin "5") (pinfunction "5_5") (pintype "bidirectional"))
      (node (ref "R49") (pin "1") (pinfunction "1_1") (pintype "passive"))
      (node (ref "U1") (pin "29") (pinfunction "PC6(/RESET)_29") (pintype "bidirectional"))
    )
    (net (code "34") (name "/RXD") (class "Default")
      (node (ref "IC5") (pin "1") (pinfunction "RO_1") (pintype "output"))
      (node (ref "U1") (pin "30") (pinfunction "PD0(RXD)_30") (pintype "bidirectional"))
    )
    (net (code "35") (name "/SCK") (class "Default")
      (node (ref "J1") (pin "3") (pinfunction "3_3") (pintype "bidirectional"))
      (node (ref "U$10") (pin "4") (pinfunction "VIB_4") (pintype "input"))
      (node (ref "U1") (pin "17") (pinfunction "PB5(SCK)_17") (pintype "bidirectional"))
    )
    (net (code "36") (name "/SCLK") (class "Default")
      (node (ref "U$1") (pin "8") (pinfunction "SCLK_8") (pintype "bidirectional"))
      (node (ref "U$10") (pin "13") (pinfunction "VOB_13") (pintype "tri_state"))
      (node (ref "U$4") (pin "8") (pinfunction "SCLK_8") (pintype "bidirectional"))
      (node (ref "U$6") (pin "8") (pinfunction "SCLK_8") (pintype "bidirectional"))
      (node (ref "U$8") (pin "8") (pinfunction "SCLK_8") (pintype "bidirectional"))
    )
    (net (code "37") (name "/SDI") (class "Default")
      (node (ref "U$1") (pin "9") (pinfunction "DIN_9") (pintype "bidirectional"))
      (node (ref "U$10") (pin "14") (pinfunction "VOA_14") (pintype "tri_state"))
      (node (ref "U$4") (pin "9") (pinfunction "DIN_9") (pintype "bidirectional"))
      (node (ref "U$6") (pin "9") (pinfunction "DIN_9") (pintype "bidirectional"))
      (node (ref "U$8") (pin "9") (pinfunction "DIN_9") (pintype "bidirectional"))
    )
    (net (code "38") (name "/SDO") (class "Default")
      (node (ref "U$1") (pin "10") (pinfunction "SDO_10") (pintype "bidirectional"))
      (node (ref "U$10") (pin "11") (pinfunction "VID_11") (pintype "input"))
      (node (ref "U$4") (pin "10") (pinfunction "SDO_10") (pintype "bidirectional"))
      (node (ref "U$6") (pin "10") (pinfunction "SDO_10") (pintype "bidirectional"))
      (node (ref "U$8") (pin "10") (pinfunction "SDO_10") (pintype "bidirectional"))
    )
    (net (code "39") (name "/TXD") (class "Default")
      (node (ref "IC5") (pin "4") (pinfunction "DI_4") (pintype "input"))
      (node (ref "U1") (pin "31") (pinfunction "PD1(TXD)_31") (pintype "bidirectional"))
    )
    (net (code "40") (name "GND") (class "Default")
      (node (ref "C57") (pin "2") (pinfunction "2_2") (pintype "passive"))
      (node (ref "C58") (pin "2") (pinfunction "2_2") (pintype "passive"))
      (node (ref "C59") (pin "2") (pinfunction "2_2") (pintype "passive"))
      (node (ref "C60") (pin "2") (pinfunction "2_2") (pintype "passive"))
      (node (ref "C61") (pin "2") (pinfunction "2_2") (pintype "passive"))
      (node (ref "C62") (pin "2") (pinfunction "2_2") (pintype "passive"))
      (node (ref "IC2") (pin "1") (pinfunction "OC_1") (pintype "input"))
      (node (ref "IC2") (pin "10") (pinfunction "GND_10") (pintype "power_in"))
      (node (ref "IC3") (pin "10") (pinfunction "GND_10") (pintype "power_in"))
      (node (ref "IC5") (pin "5") (pinfunction "GND_5") (pintype "power_in"))
      (node (ref "J1") (pin "6") (pinfunction "6_6") (pintype "bidirectional"))
      (node (ref "JP2") (pin "5") (pinfunction "5_5") (pintype "passive"))
      (node (ref "JP2") (pin "6") (pinfunction "6_6") (pintype "passive"))
      (node (ref "JP2") (pin "7") (pinfunction "7_7") (pintype "passive"))
      (node (ref "JP2") (pin "8") (pinfunction "8_8") (pintype "passive"))
      (node (ref "JP3") (pin "5") (pinfunction "5_5") (pintype "passive"))
      (node (ref "JP3") (pin "6") (pinfunction "6_6") (pintype "passive"))
      (node (ref "JP3") (pin "7") (pinfunction "7_7") (pintype "passive"))
      (node (ref "JP3") (pin "8") (pinfunction "8_8") (pintype "passive"))
      (node (ref "OK1") (pin "2") (pinfunction "C_2") (pintype "passive"))
      (node (ref "OK1") (pin "4") (pinfunction "C_4") (pintype "passive"))
      (node (ref "OK1") (pin "6") (pinfunction "C_6") (pintype "passive"))
      (node (ref "OK1") (pin "8") (pinfunction "C_8") (pintype "passive"))
      (node (ref "Q2") (pin "2") (pinfunction "GND_2") (pintype "power_in"))
      (node (ref "U$10") (pin "2") (pinfunction "GND1_2") (pintype "input"))
      (node (ref "U$10") (pin "8") (pinfunction "GND1_8") (pintype "input"))
      (node (ref "U1") (pin "21") (pinfunction "GND_21") (pintype "bidirectional"))
      (node (ref "U1") (pin "3") (pinfunction "GND_3") (pintype "bidirectional"))
      (node (ref "U1") (pin "5") (pinfunction "GND_5") (pintype "bidirectional"))
    )
    (net (code "41") (name "GNDIO") (class "Default")
      (node (ref "C1") (pin "2") (pinfunction "2_2") (pintype "passive"))
      (node (ref "C10") (pin "2") (pinfunction "2_2") (pintype "passive"))
      (node (ref "C12") (pin "2") (pinfunction "2_2") (pintype "passive"))
      (node (ref "C13") (pin "2") (pinfunction "2_2") (pintype "passive"))
      (node (ref "C14") (pin "2") (pinfunction "2_2") (pintype "passive"))
      (node (ref "C15") (pin "2") (pinfunction "2_2") (pintype "passive"))
      (node (ref "C16") (pin "2") (pinfunction "2_2") (pintype "passive"))
      (node (ref "C17") (pin "2") (pinfunction "2_2") (pintype "passive"))
      (node (ref "C18") (pin "2") (pinfunction "2_2") (pintype "passive"))
      (node (ref "C19") (pin "2") (pinfunction "2_2") (pintype "passive"))
      (node (ref "C2") (pin "2") (pinfunction "2_2") (pintype "passive"))
      (node (ref "C20") (pin "2") (pinfunction "2_2") (pintype "passive"))
      (node (ref "C21") (pin "2") (pinfunction "2_2") (pintype "passive"))
      (node (ref "C22") (pin "2") (pinfunction "2_2") (pintype "passive"))
      (node (ref "C24") (pin "2") (pinfunction "2_2") (pintype "passive"))
      (node (ref "C25") (pin "2") (pinfunction "2_2") (pintype "passive"))
      (node (ref "C26") (pin "2") (pinfunction "2_2") (pintype "passive"))
      (node (ref "C27") (pin "2") (pinfunction "2_2") (pintype "passive"))
      (node (ref "C28") (pin "2") (pinfunction "2_2") (pintype "passive"))
      (node (ref "C29") (pin "2") (pinfunction "2_2") (pintype "passive"))
      (node (ref "C3") (pin "2") (pinfunction "2_2") (pintype "passive"))
      (node (ref "C30") (pin "2") (pinfunction "2_2") (pintype "passive"))
      (node (ref "C31") (pin "2") (pinfunction "2_2") (pintype "passive"))
      (node (ref "C32") (pin "2") (pinfunction "2_2") (pintype "passive"))
      (node (ref "C33") (pin "2") (pinfunction "2_2") (pintype "passive"))
      (node (ref "C34") (pin "2") (pinfunction "2_2") (pintype "passive"))
      (node (ref "C36") (pin "2") (pinfunction "2_2") (pintype "passive"))
      (node (ref "C37") (pin "2") (pinfunction "2_2") (pintype "passive"))
      (node (ref "C38") (pin "2") (pinfunction "2_2") (pintype "passive"))
      (node (ref "C39") (pin "2") (pinfunction "2_2") (pintype "passive"))
      (node (ref "C4") (pin "2") (pinfunction "2_2") (pintype "passive"))
      (node (ref "C40") (pin "2") (pinfunction "2_2") (pintype "passive"))
      (node (ref "C41") (pin "2") (pinfunction "2_2") (pintype "passive"))
      (node (ref "C42") (pin "2") (pinfunction "2_2") (pintype "passive"))
      (node (ref "C43") (pin "2") (pinfunction "2_2") (pintype "passive"))
      (node (ref "C44") (pin "2") (pinfunction "2_2") (pintype "passive"))
      (node (ref "C45") (pin "2") (pinfunction "2_2") (pintype "passive"))
      (node (ref "C46") (pin "2") (pinfunction "2_2") (pintype "passive"))
      (node (ref "C48") (pin "2") (pinfunction "2_2") (pintype "passive"))
      (node (ref "C49") (pin "-") (pinfunction "-_-") (pintype "passive"))
      (node (ref "C5") (pin "2") (pinfunction "2_2") (pintype "passive"))
      (node (ref "C50") (pin "+") (pinfunction "+_+") (pintype "passive"))
      (node (ref "C51") (pin "1") (pinfunction "1_1") (pintype "passive"))
      (node (ref "C52") (pin "2") (pinfunction "2_2") (pintype "passive"))
      (node (ref "C53") (pin "2") (pinfunction "2_2") (pintype "passive"))
      (node (ref "C54") (pin "1") (pinfunction "1_1") (pintype "passive"))
      (node (ref "C55") (pin "2") (pinfunction "2_2") (pintype "passive"))
      (node (ref "C56") (pin "2") (pinfunction "2_2") (pintype "passive"))
      (node (ref "C6") (pin "2") (pinfunction "2_2") (pintype "passive"))
      (node (ref "C7") (pin "2") (pinfunction "2_2") (pintype "passive"))
      (node (ref "C8") (pin "2") (pinfunction "2_2") (pintype "passive"))
      (node (ref "C9") (pin "2") (pinfunction "2_2") (pintype "passive"))
      (node (ref "IC1") (pin "2") (pinfunction "GND_2") (pintype "passive"))
      (node (ref "IC1") (pin "2@1") (pinfunction "GND_2@1") (pintype "passive"))
      (node (ref "R1") (pin "1") (pinfunction "1_1") (pintype "passive"))
      (node (ref "R2") (pin "1") (pinfunction "1_1") (pintype "passive"))
      (node (ref "R3") (pin "1") (pinfunction "1_1") (pintype "passive"))
      (node (ref "R4") (pin "1") (pinfunction "1_1") (pintype "passive"))
      (node (ref "U$1") (pin "11") (pinfunction "GND_11") (pintype "bidirectional"))
      (node (ref "U$1") (pin "12") (pinfunction "GND_12") (pintype "bidirectional"))
      (node (ref "U$1") (pin "23") (pinfunction "-VSENSE_23") (pintype "bidirectional"))
      (node (ref "U$1") (pin "4") (pinfunction "GND_4") (pintype "bidirectional"))
      (node (ref "U$10") (pin "15") (pinfunction "GND2_15") (pintype "input"))
      (node (ref "U$10") (pin "9") (pinfunction "GND2_9") (pintype "input"))
      (node (ref "U$3") (pin "4") (pinfunction "GND_4") (pintype "bidirectional"))
      (node (ref "U$4") (pin "11") (pinfunction "GND_11") (pintype "bidirectional"))
      (node (ref "U$4") (pin "12") (pinfunction "GND_12") (pintype "bidirectional"))
      (node (ref "U$4") (pin "23") (pinfunction "-VSENSE_23") (pintype "bidirectional"))
      (node (ref "U$4") (pin "4") (pinfunction "GND_4") (pintype "bidirectional"))
      (node (ref "U$6") (pin "11") (pinfunction "GND_11") (pintype "bidirectional"))
      (node (ref "U$6") (pin "12") (pinfunction "GND_12") (pintype "bidirectional"))
      (node (ref "U$6") (pin "23") (pinfunction "-VSENSE_23") (pintype "bidirectional"))
      (node (ref "U$6") (pin "4") (pinfunction "GND_4") (pintype "bidirectional"))
      (node (ref "U$8") (pin "11") (pinfunction "GND_11") (pintype "bidirectional"))
      (node (ref "U$8") (pin "12") (pinfunction "GND_12") (pintype "bidirectional"))
      (node (ref "U$8") (pin "23") (pinfunction "-VSENSE_23") (pintype "bidirectional"))
      (node (ref "U$8") (pin "4") (pinfunction "GND_4") (pintype "bidirectional"))
      (node (ref "X1") (pin "1.1") (pinfunction "1_1.1") (pintype "bidirectional"))
      (node (ref "X1") (pin "1.2") (pinfunction "1_1.2") (pintype "bidirectional"))
      (node (ref "X2") (pin "1.1") (pinfunction "1_1.1") (pintype "bidirectional"))
      (node (ref "X2") (pin "1.2") (pinfunction "1_1.2") (pintype "bidirectional"))
      (node (ref "X3") (pin "1.1") (pinfunction "1_1.1") (pintype "bidirectional"))
      (node (ref "X3") (pin "1.2") (pinfunction "1_1.2") (pintype "bidirectional"))
      (node (ref "X4") (pin "1.1") (pinfunction "1_1.1") (pintype "bidirectional"))
      (node (ref "X4") (pin "1.2") (pinfunction "1_1.2") (pintype "bidirectional"))
    )
    (net (code "42") (name "Net-(D1-PadC)") (class "Default")
      (node (ref "D1") (pin "C") (pinfunction "C_C") (pintype "passive"))
      (node (ref "D2") (pin "A") (pinfunction "A_A") (pintype "passive"))
      (node (ref "R18") (pin "2") (pinfunction "2_2") (pintype "passive"))
    )
    (net (code "43") (name "Net-(D11--)") (class "Default")
      (node (ref "D11") (pin "C") (pinfunction "-_C") (pintype "passive"))
      (node (ref "U$19") (pin "2") (pinfunction "2_2") (pintype "passive"))
    )
    (net (code "44") (name "Net-(D12--)") (class "Default")
      (node (ref "D12") (pin "C") (pinfunction "-_C") (pintype "passive"))
      (node (ref "U$19") (pin "4") (pinfunction "4_4") (pintype "passive"))
    )
    (net (code "45") (name "Net-(D13--)") (class "Default")
      (node (ref "D13") (pin "C") (pinfunction "-_C") (pintype "passive"))
      (node (ref "U$19") (pin "8") (pinfunction "8_8") (pintype "passive"))
    )
    (net (code "46") (name "Net-(D14--)") (class "Default")
      (node (ref "D14") (pin "C") (pinfunction "-_C") (pintype "passive"))
      (node (ref "U$19") (pin "1") (pinfunction "1_1") (pintype "passive"))
    )
    (net (code "47") (name "Net-(D15--)") (class "Default")
      (node (ref "D15") (pin "C") (pinfunction "-_C") (pintype "passive"))
      (node (ref "U$20") (pin "1") (pinfunction "1_1") (pintype "passive"))
    )
    (net (code "48") (name "Net-(D16--)") (class "Default")
      (node (ref "D16") (pin "C") (pinfunction "-_C") (pintype "passive"))
      (node (ref "U$20") (pin "2") (pinfunction "2_2") (pintype "passive"))
    )
    (net (code "49") (name "Net-(D17--)") (class "Default")
      (node (ref "D17") (pin "C") (pinfunction "-_C") (pintype "passive"))
      (node (ref "U$20") (pin "4") (pinfunction "4_4") (pintype "passive"))
    )
    (net (code "50") (name "Net-(D18--)") (class "Default")
      (node (ref "D18") (pin "C") (pinfunction "-_C") (pintype "passive"))
      (node (ref "U$20") (pin "8") (pinfunction "8_8") (pintype "passive"))
    )
    (net (code "51") (name "Net-(IC2A-1Q)") (class "Default")
      (node (ref "IC2") (pin "19") (pinfunction "1Q_19") (pintype "tri_state"))
      (node (ref "R13") (pin "1") (pinfunction "1_1") (pintype "passive"))
    )
    (net (code "52") (name "Net-(IC2A-2Q)") (class "Default")
      (node (ref "IC2") (pin "18") (pinfunction "2Q_18") (pintype "tri_state"))
      (node (ref "R14") (pin "1") (pinfunction "1_1") (pintype "passive"))
    )
    (net (code "53") (name "Net-(IC2A-3Q)") (class "Default")
      (node (ref "IC2") (pin "17") (pinfunction "3Q_17") (pintype "tri_state"))
      (node (ref "R15") (pin "1") (pinfunction "1_1") (pintype "passive"))
    )
    (net (code "54") (name "Net-(IC2A-4Q)") (class "Default")
      (node (ref "IC2") (pin "16") (pinfunction "4Q_16") (pintype "tri_state"))
      (node (ref "R16") (pin "1") (pinfunction "1_1") (pintype "passive"))
    )
    (net (code "55") (name "Net-(IC2A-5Q)") (class "Default")
      (node (ref "IC2") (pin "15") (pinfunction "5Q_15") (pintype "tri_state"))
      (node (ref "R17") (pin "1") (pinfunction "1_1") (pintype "passive"))
    )
    (net (code "56") (name "Net-(IC2A-6Q)") (class "Default")
      (node (ref "IC2") (pin "14") (pinfunction "6Q_14") (pintype "tri_state"))
      (node (ref "R19") (pin "1") (pinfunction "1_1") (pintype "passive"))
    )
    (net (code "57") (name "Net-(IC2A-7Q)") (class "Default")
      (node (ref "IC2") (pin "13") (pinfunction "7Q_13") (pintype "tri_state"))
      (node (ref "R20") (pin "1") (pinfunction "1_1") (pintype "passive"))
    )
    (net (code "58") (name "Net-(IC2A-8Q)") (class "Default")
      (node (ref "IC2") (pin "12") (pinfunction "8Q_12") (pintype "tri_state"))
      (node (ref "R21") (pin "1") (pinfunction "1_1") (pintype "passive"))
    )
    (net (code "59") (name "Net-(IC3A-1D)") (class "Default")
      (node (ref "IC3") (pin "2") (pinfunction "1D_2") (pintype "input"))
      (node (ref "OK2") (pin "15") (pinfunction "EMIT_15") (pintype "passive"))
    )
    (net (code "60") (name "Net-(IC3A-2D)") (class "Default")
      (node (ref "IC3") (pin "3") (pinfunction "2D_3") (pintype "input"))
      (node (ref "OK2") (pin "13") (pinfunction "EMIT_13") (pintype "passive"))
    )
    (net (code "61") (name "Net-(IC3A-3D)") (class "Default")
      (node (ref "IC3") (pin "4") (pinfunction "3D_4") (pintype "input"))
      (node (ref "OK2") (pin "11") (pinfunction "EMIT_11") (pintype "passive"))
    )
    (net (code "62") (name "Net-(IC3A-4D)") (class "Default")
      (node (ref "IC3") (pin "5") (pinfunction "4D_5") (pintype "input"))
      (node (ref "OK2") (pin "9") (pinfunction "EMIT_9") (pintype "passive"))
    )
    (net (code "63") (name "Net-(JP1-Pad2)") (class "Default")
      (node (ref "JP1") (pin "2") (pinfunction "2_2") (pintype "passive"))
      (node (ref "R50") (pin "1") (pinfunction "1_1") (pintype "passive"))
    )
    (net (code "64") (name "Net-(L4-Pad1)") (class "Default")
      (node (ref "L4") (pin "1") (pinfunction "1_1") (pintype "passive"))
      (node (ref "R18") (pin "1") (pinfunction "1_1") (pintype "passive"))
    )
    (net (code "65") (name "Net-(L4-Pad2)") (class "Default")
      (node (ref "L4") (pin "2") (pinfunction "2_2") (pintype "passive"))
      (node (ref "X5") (pin "2.1") (pinfunction "2_2.1") (pintype "bidirectional"))
      (node (ref "X5") (pin "2.2") (pinfunction "2_2.2") (pintype "bidirectional"))
    )
    (net (code "66") (name "Net-(L5-Pad2)") (class "Default")
      (node (ref "L5") (pin "2") (pinfunction "2_2") (pintype "passive"))
      (node (ref "X5") (pin "1.1") (pinfunction "1_1.1") (pintype "bidirectional"))
      (node (ref "X5") (pin "1.2") (pinfunction "1_1.2") (pintype "bidirectional"))
    )
    (net (code "67") (name "Net-(LED1-CG)") (class "Default")
      (node (ref "LED1") (pin "1") (pinfunction "CG_1") (pintype "passive"))
      (node (ref "R14") (pin "2") (pinfunction "2_2") (pintype "passive"))
    )
    (net (code "68") (name "Net-(LED1-CR)") (class "Default")
      (node (ref "LED1") (pin "3") (pinfunction "CR_3") (pintype "passive"))
      (node (ref "R19") (pin "2") (pinfunction "2_2") (pintype "passive"))
    )
    (net (code "69") (name "Net-(LED2-CG)") (class "Default")
      (node (ref "LED2") (pin "1") (pinfunction "CG_1") (pintype "passive"))
      (node (ref "R15") (pin "2") (pinfunction "2_2") (pintype "passive"))
    )
    (net (code "70") (name "Net-(LED2-CR)") (class "Default")
      (node (ref "LED2") (pin "3") (pinfunction "CR_3") (pintype "passive"))
      (node (ref "R20") (pin "2") (pinfunction "2_2") (pintype "passive"))
    )
    (net (code "71") (name "Net-(LED3-CG)") (class "Default")
      (node (ref "LED3") (pin "1") (pinfunction "CG_1") (pintype "passive"))
      (node (ref "R16") (pin "2") (pinfunction "2_2") (pintype "passive"))
    )
    (net (code "72") (name "Net-(LED3-CR)") (class "Default")
      (node (ref "LED3") (pin "3") (pinfunction "CR_3") (pintype "passive"))
      (node (ref "R21") (pin "2") (pinfunction "2_2") (pintype "passive"))
    )
    (net (code "73") (name "Net-(LED8-CG)") (class "Default")
      (node (ref "LED8") (pin "1") (pinfunction "CG_1") (pintype "passive"))
      (node (ref "R13") (pin "2") (pinfunction "2_2") (pintype "passive"))
    )
    (net (code "74") (name "Net-(LED8-CR)") (class "Default")
      (node (ref "LED8") (pin "3") (pinfunction "CR_3") (pintype "passive"))
      (node (ref "R17") (pin "2") (pinfunction "2_2") (pintype "passive"))
    )
    (net (code "75") (name "Net-(OK1A-A)") (class "Default")
      (node (ref "OK1") (pin "1") (pinfunction "A_1") (pintype "passive"))
      (node (ref "R5") (pin "1") (pinfunction "1_1") (pintype "passive"))
    )
    (net (code "76") (name "Net-(OK1B-A)") (class "Default")
      (node (ref "OK1") (pin "3") (pinfunction "A_3") (pintype "passive"))
      (node (ref "R6") (pin "1") (pinfunction "1_1") (pintype "passive"))
    )
    (net (code "77") (name "Net-(OK1C-A)") (class "Default")
      (node (ref "OK1") (pin "5") (pinfunction "A_5") (pintype "passive"))
      (node (ref "R7") (pin "1") (pinfunction "1_1") (pintype "passive"))
    )
    (net (code "78") (name "Net-(OK1D-A)") (class "Default")
      (node (ref "OK1") (pin "7") (pinfunction "A_7") (pintype "passive"))
      (node (ref "R8") (pin "1") (pinfunction "1_1") (pintype "passive"))
    )
    (net (code "79") (name "Net-(OK2A-A)") (class "Default")
      (node (ref "OK2") (pin "1") (pinfunction "A_1") (pintype "passive"))
      (node (ref "R9") (pin "2") (pinfunction "2_2") (pintype "passive"))
    )
    (net (code "80") (name "Net-(OK2B-A)") (class "Default")
      (node (ref "OK2") (pin "3") (pinfunction "A_3") (pintype "passive"))
      (node (ref "R10") (pin "2") (pinfunction "2_2") (pintype "passive"))
    )
    (net (code "81") (name "Net-(OK2C-A)") (class "Default")
      (node (ref "OK2") (pin "5") (pinfunction "A_5") (pintype "passive"))
      (node (ref "R11") (pin "2") (pinfunction "2_2") (pintype "passive"))
    )
    (net (code "82") (name "Net-(OK2D-A)") (class "Default")
      (node (ref "OK2") (pin "7") (pinfunction "A_7") (pintype "passive"))
      (node (ref "R12") (pin "2") (pinfunction "2_2") (pintype "passive"))
    )
    (net (code "83") (name "Net-(Q2-OUT)") (class "Default")
      (node (ref "Q2") (pin "3") (pinfunction "OUT_3") (pintype "output"))
      (node (ref "U1") (pin "7") (pinfunction "PB6(XTAL1/TOSC1)_7") (pintype "bidirectional"))
    )
    (net (code "84") (name "Net-(U$1-+VSENSE)") (class "Default")
      (node (ref "U$1") (pin "22") (pinfunction "+VSENSE_22") (pintype "bidirectional"))
      (node (ref "U$2") (pin "1") (pinfunction "OUT_1") (pintype "output"))
      (node (ref "U$2") (pin "4") (pinfunction "-IN_4") (pintype "input"))
    )
    (net (code "85") (name "Net-(U$1-CMP)") (class "Default")
      (node (ref "C11") (pin "1") (pinfunction "1_1") (pintype "passive"))
      (node (ref "U$1") (pin "17") (pinfunction "CMP_17") (pintype "bidirectional"))
    )
    (net (code "86") (name "Net-(U$1-HART-IN)") (class "Default")
      (node (ref "C10") (pin "1") (pinfunction "1_1") (pintype "passive"))
      (node (ref "U$1") (pin "18") (pinfunction "HART-IN_18") (pintype "bidirectional"))
    )
    (net (code "87") (name "Net-(U$1-IOUT)") (class "Default")
      (node (ref "C11") (pin "2") (pinfunction "2_2") (pintype "passive"))
      (node (ref "U$1") (pin "19") (pinfunction "IOUT_19") (pintype "bidirectional"))
      (node (ref "U$1") (pin "21") (pinfunction "VOUT_21") (pintype "bidirectional"))
      (node (ref "U$2") (pin "3") (pinfunction "+IN_3") (pintype "input"))
      (node (ref "X1") (pin "2.1") (pinfunction "2_2.1") (pintype "bidirectional"))
      (node (ref "X1") (pin "2.2") (pinfunction "2_2.2") (pintype "bidirectional"))
    )
    (net (code "88") (name "Net-(U$1-REFIN)") (class "Default")
      (node (ref "C9") (pin "1") (pinfunction "1_1") (pintype "passive"))
      (node (ref "U$1") (pin "14") (pinfunction "REFOUT_14") (pintype "bidirectional"))
      (node (ref "U$1") (pin "15") (pinfunction "REFIN_15") (pintype "bidirectional"))
    )
    (net (code "89") (name "Net-(U$3-VIN+)") (class "Default")
      (node (ref "D2") (pin "C") (pinfunction "C_C") (pintype "passive"))
      (node (ref "U$3") (pin "1") (pinfunction "VIN+_1") (pintype "bidirectional"))
    )
    (net (code "90") (name "Net-(U$3-VIN-)") (class "Default")
      (node (ref "D1") (pin "A") (pinfunction "A_A") (pintype "passive"))
      (node (ref "L5") (pin "1") (pinfunction "1_1") (pintype "passive"))
      (node (ref "U$3") (pin "2") (pinfunction "VIN-_2") (pintype "bidirectional"))
    )
    (net (code "91") (name "Net-(U$3-VOUT+)") (class "Default")
      (node (ref "L1") (pin "2") (pinfunction "2_2") (pintype "passive"))
      (node (ref "U$3") (pin "3") (pinfunction "VOUT+_3") (pintype "bidirectional"))
    )
    (net (code "92") (name "Net-(U$3-VOUT-)") (class "Default")
      (node (ref "L2") (pin "2") (pinfunction "2_2") (pintype "passive"))
      (node (ref "U$3") (pin "5") (pinfunction "VOUT-_5") (pintype "bidirectional"))
    )
    (net (code "93") (name "Net-(U$4-+VSENSE)") (class "Default")
      (node (ref "U$4") (pin "22") (pinfunction "+VSENSE_22") (pintype "bidirectional"))
      (node (ref "U$5") (pin "1") (pinfunction "OUT_1") (pintype "output"))
      (node (ref "U$5") (pin "4") (pinfunction "-IN_4") (pintype "input"))
    )
    (net (code "94") (name "Net-(U$4-CMP)") (class "Default")
      (node (ref "C23") (pin "1") (pinfunction "1_1") (pintype "passive"))
      (node (ref "U$4") (pin "17") (pinfunction "CMP_17") (pintype "bidirectional"))
    )
    (net (code "95") (name "Net-(U$4-HART-IN)") (class "Default")
      (node (ref "C22") (pin "1") (pinfunction "1_1") (pintype "passive"))
      (node (ref "U$4") (pin "18") (pinfunction "HART-IN_18") (pintype "bidirectional"))
    )
    (net (code "96") (name "Net-(U$4-IOUT)") (class "Default")
      (node (ref "C23") (pin "2") (pinfunction "2_2") (pintype "passive"))
      (node (ref "U$4") (pin "19") (pinfunction "IOUT_19") (pintype "bidirectional"))
      (node (ref "U$4") (pin "21") (pinfunction "VOUT_21") (pintype "bidirectional"))
      (node (ref "U$5") (pin "3") (pinfunction "+IN_3") (pintype "input"))
      (node (ref "X2") (pin "2.1") (pinfunction "2_2.1") (pintype "bidirectional"))
      (node (ref "X2") (pin "2.2") (pinfunction "2_2.2") (pintype "bidirectional"))
    )
    (net (code "97") (name "Net-(U$4-REFIN)") (class "Default")
      (node (ref "C21") (pin "1") (pinfunction "1_1") (pintype "passive"))
      (node (ref "U$4") (pin "14") (pinfunction "REFOUT_14") (pintype "bidirectional"))
      (node (ref "U$4") (pin "15") (pinfunction "REFIN_15") (pintype "bidirectional"))
    )
    (net (code "98") (name "Net-(U$6-+VSENSE)") (class "Default")
      (node (ref "U$6") (pin "22") (pinfunction "+VSENSE_22") (pintype "bidirectional"))
      (node (ref "U$7") (pin "1") (pinfunction "OUT_1") (pintype "output"))
      (node (ref "U$7") (pin "4") (pinfunction "-IN_4") (pintype "input"))
    )
    (net (code "99") (name "Net-(U$6-CMP)") (class "Default")
      (node (ref "C35") (pin "1") (pinfunction "1_1") (pintype "passive"))
      (node (ref "U$6") (pin "17") (pinfunction "CMP_17") (pintype "bidirectional"))
    )
    (net (code "100") (name "Net-(U$6-HART-IN)") (class "Default")
      (node (ref "C34") (pin "1") (pinfunction "1_1") (pintype "passive"))
      (node (ref "U$6") (pin "18") (pinfunction "HART-IN_18") (pintype "bidirectional"))
    )
    (net (code "101") (name "Net-(U$6-IOUT)") (class "Default")
      (node (ref "C35") (pin "2") (pinfunction "2_2") (pintype "passive"))
      (node (ref "U$6") (pin "19") (pinfunction "IOUT_19") (pintype "bidirectional"))
      (node (ref "U$6") (pin "21") (pinfunction "VOUT_21") (pintype "bidirectional"))
      (node (ref "U$7") (pin "3") (pinfunction "+IN_3") (pintype "input"))
      (node (ref "X3") (pin "2.1") (pinfunction "2_2.1") (pintype "bidirectional"))
      (node (ref "X3") (pin "2.2") (pinfunction "2_2.2") (pintype "bidirectional"))
    )
    (net (code "102") (name "Net-(U$6-REFIN)") (class "Default")
      (node (ref "C33") (pin "1") (pinfunction "1_1") (pintype "passive"))
      (node (ref "U$6") (pin "14") (pinfunction "REFOUT_14") (pintype "bidirectional"))
      (node (ref "U$6") (pin "15") (pinfunction "REFIN_15") (pintype "bidirectional"))
    )
    (net (code "103") (name "Net-(U$8-+VSENSE)") (class "Default")
      (node (ref "U$8") (pin "22") (pinfunction "+VSENSE_22") (pintype "bidirectional"))
      (node (ref "U$9") (pin "1") (pinfunction "OUT_1") (pintype "output"))
      (node (ref "U$9") (pin "4") (pinfunction "-IN_4") (pintype "input"))
    )
    (net (code "104") (name "Net-(U$8-CMP)") (class "Default")
      (node (ref "C47") (pin "1") (pinfunction "1_1") (pintype "passive"))
      (node (ref "U$8") (pin "17") (pinfunction "CMP_17") (pintype "bidirectional"))
    )
    (net (code "105") (name "Net-(U$8-HART-IN)") (class "Default")
      (node (ref "C46") (pin "1") (pinfunction "1_1") (pintype "passive"))
      (node (ref "U$8") (pin "18") (pinfunction "HART-IN_18") (pintype "bidirectional"))
    )
    (net (code "106") (name "Net-(U$8-IOUT)") (class "Default")
      (node (ref "C47") (pin "2") (pinfunction "2_2") (pintype "passive"))
      (node (ref "U$8") (pin "19") (pinfunction "IOUT_19") (pintype "bidirectional"))
      (node (ref "U$8") (pin "21") (pinfunction "VOUT_21") (pintype "bidirectional"))
      (node (ref "U$9") (pin "3") (pinfunction "+IN_3") (pintype "input"))
      (node (ref "X4") (pin "2.1") (pinfunction "2_2.1") (pintype "bidirectional"))
      (node (ref "X4") (pin "2.2") (pinfunction "2_2.2") (pintype "bidirectional"))
    )
    (net (code "107") (name "Net-(U$8-REFIN)") (class "Default")
      (node (ref "C45") (pin "1") (pinfunction "1_1") (pintype "passive"))
      (node (ref "U$8") (pin "14") (pinfunction "REFOUT_14") (pintype "bidirectional"))
      (node (ref "U$8") (pin "15") (pinfunction "REFIN_15") (pintype "bidirectional"))
    )
    (net (code "108") (name "VCC") (class "Default")
      (node (ref "C12") (pin "1") (pinfunction "1_1") (pintype "passive"))
      (node (ref "C24") (pin "1") (pinfunction "1_1") (pintype "passive"))
      (node (ref "C36") (pin "1") (pinfunction "1_1") (pintype "passive"))
      (node (ref "C48") (pin "1") (pinfunction "1_1") (pintype "passive"))
      (node (ref "C56") (pin "1") (pinfunction "1_1") (pintype "passive"))
      (node (ref "IC1") (pin "1") (pinfunction "VO_1") (pintype "passive"))
      (node (ref "OK1") (pin "10") (pinfunction "COL_10") (pintype "passive"))
      (node (ref "OK1") (pin "12") (pinfunction "COL_12") (pintype "passive"))
      (node (ref "OK1") (pin "14") (pinfunction "COL_14") (pintype "passive"))
      (node (ref "OK1") (pin "16") (pinfunction "COL_16") (pintype "passive"))
      (node (ref "R10") (pin "1") (pinfunction "1_1") (pintype "passive"))
      (node (ref "R11") (pin "1") (pinfunction "1_1") (pintype "passive"))
      (node (ref "R12") (pin "1") (pinfunction "1_1") (pintype "passive"))
      (node (ref "R9") (pin "1") (pinfunction "1_1") (pintype "passive"))
      (node (ref "U$1") (pin "2") (pinfunction "DVDD_2") (pintype "bidirectional"))
      (node (ref "U$10") (pin "16") (pinfunction "VDD2_16") (pintype "input"))
      (node (ref "U$4") (pin "2") (pinfunction "DVDD_2") (pintype "bidirectional"))
      (node (ref "U$6") (pin "2") (pinfunction "DVDD_2") (pintype "bidirectional"))
      (node (ref "U$8") (pin "2") (pinfunction "DVDD_2") (pintype "bidirectional"))
    )
    (net (code "109") (name "unconnected-(IC3A-5D-Pad6)") (class "Default")
      (node (ref "IC3") (pin "6") (pinfunction "5D_6") (pintype "input"))
    )
    (net (code "110") (name "unconnected-(IC3A-5Q-Pad15)") (class "Default")
      (node (ref "IC3") (pin "15") (pinfunction "5Q_15") (pintype "tri_state"))
    )
    (net (code "111") (name "unconnected-(IC3A-6D-Pad7)") (class "Default")
      (node (ref "IC3") (pin "7") (pinfunction "6D_7") (pintype "input"))
    )
    (net (code "112") (name "unconnected-(IC3A-6Q-Pad14)") (class "Default")
      (node (ref "IC3") (pin "14") (pinfunction "6Q_14") (pintype "tri_state"))
    )
    (net (code "113") (name "unconnected-(IC3A-7D-Pad8)") (class "Default")
      (node (ref "IC3") (pin "8") (pinfunction "7D_8") (pintype "input"))
    )
    (net (code "114") (name "unconnected-(IC3A-7Q-Pad13)") (class "Default")
      (node (ref "IC3") (pin "13") (pinfunction "7Q_13") (pintype "tri_state"))
    )
    (net (code "115") (name "unconnected-(IC3A-8D-Pad9)") (class "Default")
      (node (ref "IC3") (pin "9") (pinfunction "8D_9") (pintype "input"))
    )
    (net (code "116") (name "unconnected-(IC3A-8Q-Pad12)") (class "Default")
      (node (ref "IC3") (pin "12") (pinfunction "8Q_12") (pintype "tri_state"))
    )
    (net (code "117") (name "unconnected-(Q2-TS-Pad1)") (class "Default")
      (node (ref "Q2") (pin "1") (pinfunction "TS_1") (pintype "passive"))
    )
    (net (code "118") (name "unconnected-(U$1-BOOST-Pad20)") (class "Default")
      (node (ref "U$1") (pin "20") (pinfunction "BOOST_20") (pintype "bidirectional"))
    )
    (net (code "119") (name "unconnected-(U$1-CLR-Pad6)") (class "Default")
      (node (ref "U$1") (pin "6") (pinfunction "CLR_6") (pintype "bidirectional"))
    )
    (net (code "120") (name "unconnected-(U$1-CLR-SEL-Pad5)") (class "Default")
      (node (ref "U$1") (pin "5") (pinfunction "CLR-SEL_5") (pintype "bidirectional"))
    )
    (net (code "121") (name "unconnected-(U$1-DVDD_SEL-Pad16)") (class "Default")
      (node (ref "U$1") (pin "16") (pinfunction "DVDD_SEL_16") (pintype "bidirectional"))
    )
    (net (code "122") (name "unconnected-(U$1-ISET-R-Pad13)") (class "Default")
      (node (ref "U$1") (pin "13") (pinfunction "ISET-R_13") (pintype "bidirectional"))
    )
    (net (code "123") (name "unconnected-(U$4-BOOST-Pad20)") (class "Default")
      (node (ref "U$4") (pin "20") (pinfunction "BOOST_20") (pintype "bidirectional"))
    )
    (net (code "124") (name "unconnected-(U$4-CLR-Pad6)") (class "Default")
      (node (ref "U$4") (pin "6") (pinfunction "CLR_6") (pintype "bidirectional"))
    )
    (net (code "125") (name "unconnected-(U$4-CLR-SEL-Pad5)") (class "Default")
      (node (ref "U$4") (pin "5") (pinfunction "CLR-SEL_5") (pintype "bidirectional"))
    )
    (net (code "126") (name "unconnected-(U$4-DVDD_SEL-Pad16)") (class "Default")
      (node (ref "U$4") (pin "16") (pinfunction "DVDD_SEL_16") (pintype "bidirectional"))
    )
    (net (code "127") (name "unconnected-(U$4-ISET-R-Pad13)") (class "Default")
      (node (ref "U$4") (pin "13") (pinfunction "ISET-R_13") (pintype "bidirectional"))
    )
    (net (code "128") (name "unconnected-(U$6-BOOST-Pad20)") (class "Default")
      (node (ref "U$6") (pin "20") (pinfunction "BOOST_20") (pintype "bidirectional"))
    )
    (net (code "129") (name "unconnected-(U$6-CLR-Pad6)") (class "Default")
      (node (ref "U$6") (pin "6") (pinfunction "CLR_6") (pintype "bidirectional"))
    )
    (net (code "130") (name "unconnected-(U$6-CLR-SEL-Pad5)") (class "Default")
      (node (ref "U$6") (pin "5") (pinfunction "CLR-SEL_5") (pintype "bidirectional"))
    )
    (net (code "131") (name "unconnected-(U$6-DVDD_SEL-Pad16)") (class "Default")
      (node (ref "U$6") (pin "16") (pinfunction "DVDD_SEL_16") (pintype "bidirectional"))
    )
    (net (code "132") (name "unconnected-(U$6-ISET-R-Pad13)") (class "Default")
      (node (ref "U$6") (pin "13") (pinfunction "ISET-R_13") (pintype "bidirectional"))
    )
    (net (code "133") (name "unconnected-(U$8-BOOST-Pad20)") (class "Default")
      (node (ref "U$8") (pin "20") (pinfunction "BOOST_20") (pintype "bidirectional"))
    )
    (net (code "134") (name "unconnected-(U$8-CLR-Pad6)") (class "Default")
      (node (ref "U$8") (pin "6") (pinfunction "CLR_6") (pintype "bidirectional"))
    )
    (net (code "135") (name "unconnected-(U$8-CLR-SEL-Pad5)") (class "Default")
      (node (ref "U$8") (pin "5") (pinfunction "CLR-SEL_5") (pintype "bidirectional"))
    )
    (net (code "136") (name "unconnected-(U$8-DVDD_SEL-Pad16)") (class "Default")
      (node (ref "U$8") (pin "16") (pinfunction "DVDD_SEL_16") (pintype "bidirectional"))
    )
    (net (code "137") (name "unconnected-(U$8-ISET-R-Pad13)") (class "Default")
      (node (ref "U$8") (pin "13") (pinfunction "ISET-R_13") (pintype "bidirectional"))
    )
    (net (code "138") (name "unconnected-(U$10-VE1-Pad7)") (class "Default")
      (node (ref "U$10") (pin "7") (pinfunction "VE1_7") (pintype "input"))
    )
    (net (code "139") (name "unconnected-(U$10-VE2-Pad10)") (class "Default")
      (node (ref "U$10") (pin "10") (pinfunction "VE2_10") (pintype "input"))
    )
    (net (code "140") (name "unconnected-(U$10-VIC-Pad5)") (class "Default")
      (node (ref "U$10") (pin "5") (pinfunction "VIC_5") (pintype "tri_state"))
    )
    (net (code "141") (name "unconnected-(U$10-VOC-Pad12)") (class "Default")
      (node (ref "U$10") (pin "12") (pinfunction "VOC_12") (pintype "input"))
    )
    (net (code "142") (name "unconnected-(U1-PB7(XTAL2{slash}TOSC2)-Pad8)") (class "Default")
      (node (ref "U1") (pin "8") (pinfunction "PB7(XTAL2/TOSC2)_8") (pintype "bidirectional"))
    )
  )
)
